# DW-01_lithium_protection.net
KiCad netlist of a schematic drawn in EAGLE
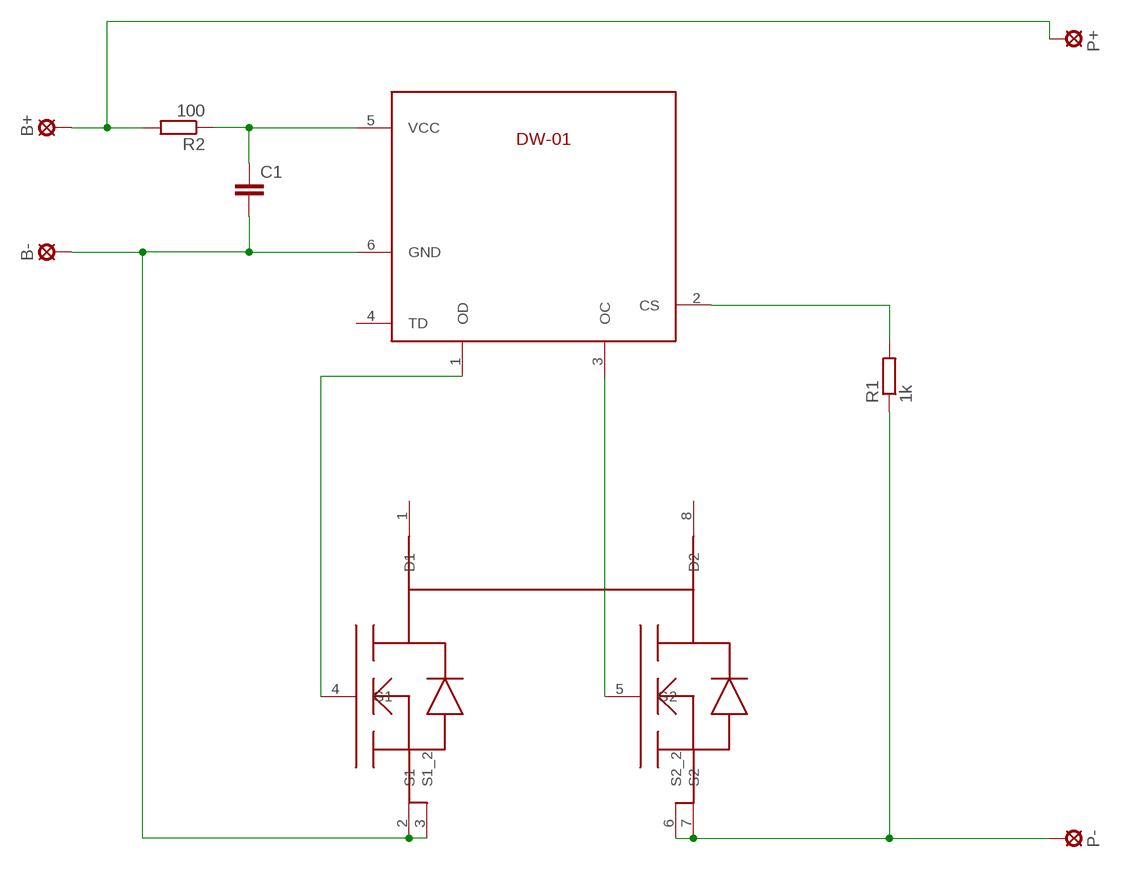
[diagram p0: schematic, sheet 1]

(export (version "E")
  (design (tool "Eeschema 10.0.6"))
  (components
    (comp (ref "B+")
      (value "LSP10")
      (footprint "eagle-import:LSP10")
      (libsource (lib "eagle-import") (part "LSP10"))
    )
    (comp (ref "B-")
      (value "LSP10")
      (footprint "eagle-import:LSP10")
      (libsource (lib "eagle-import") (part "LSP10"))
    )
    (comp (ref "C1")
      (value "C-EUC0603")
      (footprint "eagle-import:C0603")
      (libsource (lib "eagle-import") (part "C-EUC0603"))
    )
    (comp (ref "P+")
      (value "LSP10")
      (footprint "eagle-import:LSP10")
      (libsource (lib "eagle-import") (part "LSP10"))
    )
    (comp (ref "P-")
      (value "LSP10")
      (footprint "eagle-import:LSP10")
      (libsource (lib "eagle-import") (part "LSP10"))
    )
    (comp (ref "R1")
      (value "1k")
      (footprint "eagle-import:R0603")
      (libsource (lib "eagle-import") (part "R-EU_R0603"))
    )
    (comp (ref "R2")
      (value "100")
      (footprint "eagle-import:R0603")
      (libsource (lib "eagle-import") (part "R-EU_R0603"))
    )
    (comp (ref "U$1")
      (value "DW-01")
      (footprint "eagle-import:SOT23-6")
      (libsource (lib "eagle-import") (part "DW-01"))
    )
    (comp (ref "U$2")
      (value "8205A")
      (footprint "eagle-import:TSSOP8")
      (libsource (lib "eagle-import") (part "8205A"))
    )
  )
  (nets
    (net (code "1") (name "Net-(B+-PadMP)") (class "Default")
      (node (ref "B+") (pin "MP") (pinfunction "MP_MP") (pintype "passive"))
      (node (ref "P+") (pin "MP") (pinfunction "MP_MP") (pintype "passive"))
      (node (ref "R2") (pin "2") (pinfunction "2_2") (pintype "passive"))
    )
    (net (code "2") (name "Net-(U$1-CS)") (class "Default")
      (node (ref "R1") (pin "2") (pinfunction "2_2") (pintype "passive"))
      (node (ref "U$1") (pin "2") (pinfunction "CS_2") (pintype "bidirectional"))
    )
    (net (code "3") (name "Net-(U$1-GND)") (class "Default")
      (node (ref "B-") (pin "MP") (pinfunction "MP_MP") (pintype "passive"))
      (node (ref "C1") (pin "2") (pinfunction "2_2") (pintype "passive"))
      (node (ref "U$1") (pin "6") (pinfunction "GND_6") (pintype "bidirectional"))
      (node (ref "U$2") (pin "2") (pinfunction "S1_2") (pintype "bidirectional"))
      (node (ref "U$2") (pin "3") (pinfunction "S1_2_3") (pintype "bidirectional"))
    )
    (net (code "4") (name "Net-(U$1-OC)") (class "Default")
      (node (ref "U$1") (pin "3") (pinfunction "OC_3") (pintype "bidirectional"))
      (node (ref "U$2") (pin "5") (pinfunction "G2_5") (pintype "bidirectional"))
    )
    (net (code "5") (name "Net-(U$1-OD)") (class "Default")
      (node (ref "U$1") (pin "1") (pinfunction "OD_1") (pintype "bidirectional"))
      (node (ref "U$2") (pin "4") (pinfunction "G1_4") (pintype "bidirectional"))
    )
    (net (code "6") (name "Net-(U$1-VCC)") (class "Default")
      (node (ref "C1") (pin "1") (pinfunction "1_1") (pintype "passive"))
      (node (ref "R2") (pin "1") (pinfunction "1_1") (pintype "passive"))
      (node (ref "U$1") (pin "5") (pinfunction "VCC_5") (pintype "bidirectional"))
    )
    (net (code "7") (name "Net-(U$2-S2)") (class "Default")
      (node (ref "P-") (pin "MP") (pinfunction "MP_MP") (pintype "passive"))
      (node (ref "R1") (pin "1") (pinfunction "1_1") (pintype "passive"))
      (node (ref "U$2") (pin "6") (pinfunction "S2_2_6") (pintype "bidirectional"))
      (node (ref "U$2") (pin "7") (pinfunction "S2_7") (pintype "bidirectional"))
    )
    (net (code "8") (name "unconnected-(U$1-TD-Pad4)") (class "Default")
      (node (ref "U$1") (pin "4") (pinfunction "TD_4") (pintype "bidirectional"))
    )
    (net (code "9") (name "unconnected-(U$2-D1-Pad1)") (class "Default")
      (node (ref "U$2") (pin "1") (pinfunction "D1_1") (pintype "bidirectional"))
    )
    (net (code "10") (name "unconnected-(U$2-D2-Pad8)") (class "Default")
      (node (ref "U$2") (pin "8") (pinfunction "D2_8") (pintype "bidirectional"))
    )
  )
)
